# reset_button.net
KiCad netlist of a schematic drawn in EAGLE
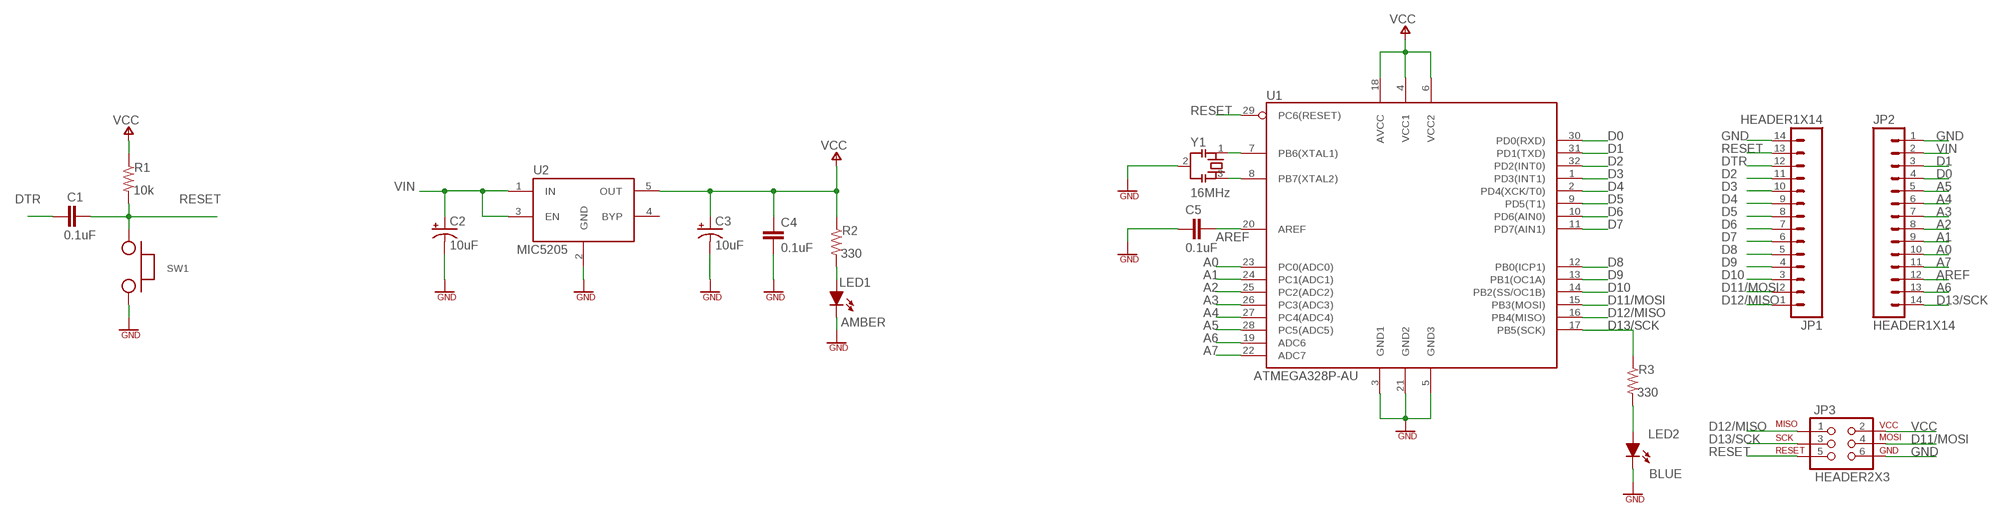
[diagram p0: schematic, sheet 1]

(export (version "E")
  (design (tool "Eeschema 10.0.6"))
  (components
    (comp (ref "C1")
      (value "0.1uF")
      (footprint "eagle-import:SMD0603")
      (libsource (lib "eagle-import") (part "CAP_0603"))
    )
    (comp (ref "C2")
      (value "10uF")
      (footprint "eagle-import:EIA3216")
      (libsource (lib "eagle-import") (part "CAP_TANT"))
    )
    (comp (ref "C3")
      (value "10uF")
      (footprint "eagle-import:EIA3216")
      (libsource (lib "eagle-import") (part "CAP_TANT"))
    )
    (comp (ref "C4")
      (value "0.1uF")
      (footprint "eagle-import:SMD0603")
      (libsource (lib "eagle-import") (part "CAP_0603"))
    )
    (comp (ref "C5")
      (value "0.1uF")
      (footprint "eagle-import:SMD0603")
      (libsource (lib "eagle-import") (part "CAP_0603"))
    )
    (comp (ref "JP1")
      (value "HEADER1X14")
      (footprint "eagle-import:1X14")
      (libsource (lib "eagle-import") (part "HEADER1X14"))
    )
    (comp (ref "JP2")
      (value "HEADER1X14")
      (footprint "eagle-import:1X14")
      (libsource (lib "eagle-import") (part "HEADER1X14"))
    )
    (comp (ref "JP3")
      (value "HEADER2X3")
      (footprint "eagle-import:2X3")
      (libsource (lib "eagle-import") (part "HEADER2X3"))
    )
    (comp (ref "LED1")
      (value "AMBER")
      (footprint "eagle-import:LED_0805")
      (libsource (lib "eagle-import") (part "LED_0805"))
    )
    (comp (ref "LED2")
      (value "BLUE")
      (footprint "eagle-import:LED_0805")
      (libsource (lib "eagle-import") (part "LED_0805"))
    )
    (comp (ref "R1")
      (value "10k")
      (footprint "eagle-import:SMD0603")
      (libsource (lib "eagle-import") (part "RES_0603"))
    )
    (comp (ref "R2")
      (value "330")
      (footprint "eagle-import:SMD0603")
      (libsource (lib "eagle-import") (part "RES_0603"))
    )
    (comp (ref "R3")
      (value "330")
      (footprint "eagle-import:SMD0603")
      (libsource (lib "eagle-import") (part "RES_0603"))
    )
    (comp (ref "SW1")
      (value "SWITCH")
      (footprint "eagle-import:SWITCH-SPST")
      (libsource (lib "eagle-import") (part "SWITCH"))
    )
    (comp (ref "U1")
      (value "ATMEGA328P-AU")
      (footprint "eagle-import:TQFP32")
      (libsource (lib "eagle-import") (part "ATMEGA328P-AU"))
    )
    (comp (ref "U2")
      (value "MIC5205")
      (footprint "eagle-import:SOT23-5")
      (libsource (lib "eagle-import") (part "MIC5205"))
    )
    (comp (ref "Y1")
      (value "16MHz")
      (footprint "eagle-import:CSTCE")
      (libsource (lib "eagle-import") (part "CSTCE"))
    )
  )
  (nets
    (net (code "1") (name "/A0") (class "Default")
      (node (ref "JP2") (pin "10") (pinfunction "10_10") (pintype "passive"))
      (node (ref "U1") (pin "23") (pinfunction "PC0(ADC0)_23") (pintype "bidirectional"))
    )
    (net (code "2") (name "/A1") (class "Default")
      (node (ref "JP2") (pin "9") (pinfunction "9_9") (pintype "passive"))
      (node (ref "U1") (pin "24") (pinfunction "PC1(ADC1)_24") (pintype "bidirectional"))
    )
    (net (code "3") (name "/A2") (class "Default")
      (node (ref "JP2") (pin "8") (pinfunction "8_8") (pintype "passive"))
      (node (ref "U1") (pin "25") (pinfunction "PC2(ADC2)_25") (pintype "bidirectional"))
    )
    (net (code "4") (name "/A3") (class "Default")
      (node (ref "JP2") (pin "7") (pinfunction "7_7") (pintype "passive"))
      (node (ref "U1") (pin "26") (pinfunction "PC3(ADC3)_26") (pintype "bidirectional"))
    )
    (net (code "5") (name "/A4") (class "Default")
      (node (ref "JP2") (pin "6") (pinfunction "6_6") (pintype "passive"))
      (node (ref "U1") (pin "27") (pinfunction "PC4(ADC4)_27") (pintype "bidirectional"))
    )
    (net (code "6") (name "/A5") (class "Default")
      (node (ref "JP2") (pin "5") (pinfunction "5_5") (pintype "passive"))
      (node (ref "U1") (pin "28") (pinfunction "PC5(ADC5)_28") (pintype "bidirectional"))
    )
    (net (code "7") (name "/A6") (class "Default")
      (node (ref "JP2") (pin "13") (pinfunction "13_13") (pintype "passive"))
      (node (ref "U1") (pin "19") (pinfunction "ADC6_19") (pintype "bidirectional"))
    )
    (net (code "8") (name "/A7") (class "Default")
      (node (ref "JP2") (pin "11") (pinfunction "11_11") (pintype "passive"))
      (node (ref "U1") (pin "22") (pinfunction "ADC7_22") (pintype "bidirectional"))
    )
    (net (code "9") (name "/AREF") (class "Default")
      (node (ref "C5") (pin "1") (pinfunction "1_1") (pintype "passive"))
      (node (ref "JP2") (pin "12") (pinfunction "12_12") (pintype "passive"))
      (node (ref "U1") (pin "20") (pinfunction "AREF_20") (pintype "bidirectional"))
    )
    (net (code "10") (name "/D0") (class "Default")
      (node (ref "JP2") (pin "4") (pinfunction "4_4") (pintype "passive"))
      (node (ref "U1") (pin "30") (pinfunction "PD0(RXD)_30") (pintype "bidirectional"))
    )
    (net (code "11") (name "/D1") (class "Default")
      (node (ref "JP2") (pin "3") (pinfunction "3_3") (pintype "passive"))
      (node (ref "U1") (pin "31") (pinfunction "PD1(TXD)_31") (pintype "bidirectional"))
    )
    (net (code "12") (name "/D2") (class "Default")
      (node (ref "JP1") (pin "11") (pinfunction "11_11") (pintype "passive"))
      (node (ref "U1") (pin "32") (pinfunction "PD2(INT0)_32") (pintype "bidirectional"))
    )
    (net (code "13") (name "/D3") (class "Default")
      (node (ref "JP1") (pin "10") (pinfunction "10_10") (pintype "passive"))
      (node (ref "U1") (pin "1") (pinfunction "PD3(INT1)_1") (pintype "bidirectional"))
    )
    (net (code "14") (name "/D4") (class "Default")
      (node (ref "JP1") (pin "9") (pinfunction "9_9") (pintype "passive"))
      (node (ref "U1") (pin "2") (pinfunction "PD4(XCK/T0)_2") (pintype "bidirectional"))
    )
    (net (code "15") (name "/D5") (class "Default")
      (node (ref "JP1") (pin "8") (pinfunction "8_8") (pintype "passive"))
      (node (ref "U1") (pin "9") (pinfunction "PD5(T1)_9") (pintype "bidirectional"))
    )
    (net (code "16") (name "/D6") (class "Default")
      (node (ref "JP1") (pin "7") (pinfunction "7_7") (pintype "passive"))
      (node (ref "U1") (pin "10") (pinfunction "PD6(AIN0)_10") (pintype "bidirectional"))
    )
    (net (code "17") (name "/D7") (class "Default")
      (node (ref "JP1") (pin "6") (pinfunction "6_6") (pintype "passive"))
      (node (ref "U1") (pin "11") (pinfunction "PD7(AIN1)_11") (pintype "bidirectional"))
    )
    (net (code "18") (name "/D8") (class "Default")
      (node (ref "JP1") (pin "5") (pinfunction "5_5") (pintype "passive"))
      (node (ref "U1") (pin "12") (pinfunction "PB0(ICP1)_12") (pintype "bidirectional"))
    )
    (net (code "19") (name "/D9") (class "Default")
      (node (ref "JP1") (pin "4") (pinfunction "4_4") (pintype "passive"))
      (node (ref "U1") (pin "13") (pinfunction "PB1(OC1A)_13") (pintype "bidirectional"))
    )
    (net (code "20") (name "/D10") (class "Default")
      (node (ref "JP1") (pin "3") (pinfunction "3_3") (pintype "passive"))
      (node (ref "U1") (pin "14") (pinfunction "PB2(SS/OC1B)_14") (pintype "bidirectional"))
    )
    (net (code "21") (name "/D11{slash}MOSI") (class "Default")
      (node (ref "JP1") (pin "2") (pinfunction "2_2") (pintype "passive"))
      (node (ref "JP3") (pin "4") (pinfunction "4_4") (pintype "passive"))
      (node (ref "U1") (pin "15") (pinfunction "PB3(MOSI)_15") (pintype "bidirectional"))
    )
    (net (code "22") (name "/D12{slash}MISO") (class "Default")
      (node (ref "JP1") (pin "1") (pinfunction "1_1") (pintype "passive"))
      (node (ref "JP3") (pin "1") (pinfunction "1_1") (pintype "passive"))
      (node (ref "U1") (pin "16") (pinfunction "PB4(MISO)_16") (pintype "bidirectional"))
    )
    (net (code "23") (name "/D13{slash}SCK") (class "Default")
      (node (ref "JP2") (pin "14") (pinfunction "14_14") (pintype "passive"))
      (node (ref "JP3") (pin "3") (pinfunction "3_3") (pintype "passive"))
      (node (ref "R3") (pin "1") (pinfunction "1_1") (pintype "passive"))
      (node (ref "U1") (pin "17") (pinfunction "PB5(SCK)_17") (pintype "bidirectional"))
    )
    (net (code "24") (name "/DTR") (class "Default")
      (node (ref "C1") (pin "1") (pinfunction "1_1") (pintype "passive"))
      (node (ref "JP1") (pin "12") (pinfunction "12_12") (pintype "passive"))
    )
    (net (code "25") (name "/RESET") (class "Default")
      (node (ref "C1") (pin "2") (pinfunction "2_2") (pintype "passive"))
      (node (ref "JP1") (pin "13") (pinfunction "13_13") (pintype "passive"))
      (node (ref "JP3") (pin "5") (pinfunction "5_5") (pintype "passive"))
      (node (ref "R1") (pin "2") (pinfunction "2_2") (pintype "passive"))
      (node (ref "SW1") (pin "1") (pinfunction "1_1") (pintype "bidirectional"))
      (node (ref "U1") (pin "29") (pinfunction "PC6(RESET)_29") (pintype "bidirectional"))
    )
    (net (code "26") (name "/VIN") (class "Default")
      (node (ref "C2") (pin "A") (pinfunction "+_A") (pintype "passive"))
      (node (ref "JP2") (pin "2") (pinfunction "2_2") (pintype "passive"))
      (node (ref "U2") (pin "1") (pinfunction "IN_1") (pintype "bidirectional"))
      (node (ref "U2") (pin "3") (pinfunction "EN_3") (pintype "bidirectional"))
    )
    (net (code "27") (name "GND") (class "Default")
      (node (ref "C2") (pin "C") (pinfunction "-_C") (pintype "passive"))
      (node (ref "C3") (pin "C") (pinfunction "-_C") (pintype "passive"))
      (node (ref "C4") (pin "2") (pinfunction "2_2") (pintype "passive"))
      (node (ref "C5") (pin "2") (pinfunction "2_2") (pintype "passive"))
      (node (ref "JP1") (pin "14") (pinfunction "14_14") (pintype "passive"))
      (node (ref "JP2") (pin "1") (pinfunction "1_1") (pintype "passive"))
      (node (ref "JP3") (pin "6") (pinfunction "6_6") (pintype "passive"))
      (node (ref "LED1") (pin "C") (pinfunction "C_C") (pintype "passive"))
      (node (ref "LED2") (pin "C") (pinfunction "C_C") (pintype "passive"))
      (node (ref "SW1") (pin "2") (pinfunction "2_2") (pintype "bidirectional"))
      (node (ref "U1") (pin "21") (pinfunction "GND2_21") (pintype "bidirectional"))
      (node (ref "U1") (pin "3") (pinfunction "GND1_3") (pintype "bidirectional"))
      (node (ref "U1") (pin "5") (pinfunction "GND3_5") (pintype "bidirectional"))
      (node (ref "U2") (pin "2") (pinfunction "GND_2") (pintype "bidirectional"))
      (node (ref "Y1") (pin "2") (pinfunction "2_2") (pintype "passive"))
    )
    (net (code "28") (name "Net-(LED1-PadA)") (class "Default")
      (node (ref "LED1") (pin "A") (pinfunction "A_A") (pintype "passive"))
      (node (ref "R2") (pin "2") (pinfunction "2_2") (pintype "passive"))
    )
    (net (code "29") (name "Net-(LED2-PadA)") (class "Default")
      (node (ref "LED2") (pin "A") (pinfunction "A_A") (pintype "passive"))
      (node (ref "R3") (pin "2") (pinfunction "2_2") (pintype "passive"))
    )
    (net (code "30") (name "Net-(U1-PB6(XTAL1))") (class "Default")
      (node (ref "U1") (pin "7") (pinfunction "PB6(XTAL1)_7") (pintype "bidirectional"))
      (node (ref "Y1") (pin "1") (pinfunction "1_1") (pintype "passive"))
    )
    (net (code "31") (name "Net-(U1-PB7(XTAL2))") (class "Default")
      (node (ref "U1") (pin "8") (pinfunction "PB7(XTAL2)_8") (pintype "bidirectional"))
      (node (ref "Y1") (pin "3") (pinfunction "3_3") (pintype "passive"))
    )
    (net (code "32") (name "VCC") (class "Default")
      (node (ref "C3") (pin "A") (pinfunction "+_A") (pintype "passive"))
      (node (ref "C4") (pin "1") (pinfunction "1_1") (pintype "passive"))
      (node (ref "JP3") (pin "2") (pinfunction "2_2") (pintype "passive"))
      (node (ref "R1") (pin "1") (pinfunction "1_1") (pintype "passive"))
      (node (ref "R2") (pin "1") (pinfunction "1_1") (pintype "passive"))
      (node (ref "U1") (pin "18") (pinfunction "AVCC_18") (pintype "bidirectional"))
      (node (ref "U1") (pin "4") (pinfunction "VCC1_4") (pintype "bidirectional"))
      (node (ref "U1") (pin "6") (pinfunction "VCC2_6") (pintype "bidirectional"))
      (node (ref "U2") (pin "5") (pinfunction "OUT_5") (pintype "bidirectional"))
    )
    (net (code "33") (name "unconnected-(U2-BYP-Pad4)") (class "Default")
      (node (ref "U2") (pin "4") (pinfunction "BYP_4") (pintype "passive"))
    )
  )
)
